# MCU.net
KiCad netlist of a schematic drawn in Altium Designer
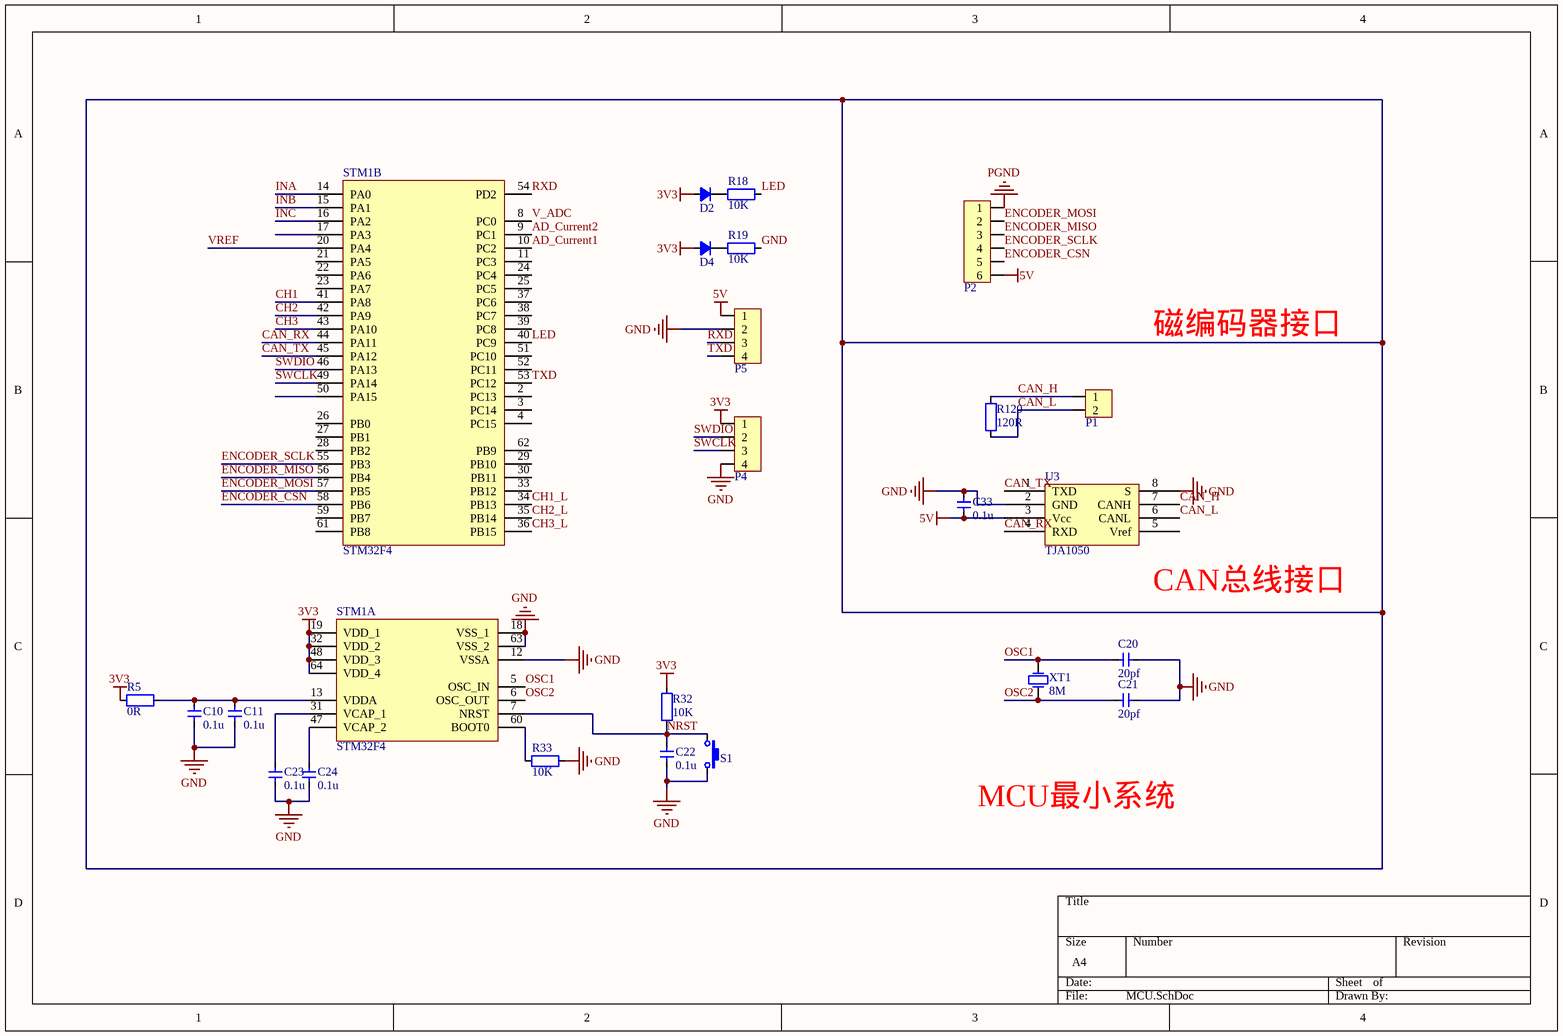
[diagram p0: MCU.SchDoc]

(export (version "E")
  (design (tool "Eeschema 10.0.6"))
  (components
    (comp (ref "C10")
      (value "0.1u")
      (footprint "PCB_PassiveCap:CAP_0603")
      (description "Capacitor")
      (fields (field (name "Comment") "Cap_0603"))
      (libsource (lib "SCH_Passive") (part "Cap_0603"))
    )
    (comp (ref "C11")
      (value "0.1u")
      (footprint "PCB_PassiveCap:CAP_0603")
      (description "Capacitor")
      (fields (field (name "Comment") "Cap_0603"))
      (libsource (lib "SCH_Passive") (part "Cap_0603"))
    )
    (comp (ref "C20")
      (value "20pf")
      (footprint "PCB_PassiveCap:CAP_0603")
      (description "Capacitor")
      (fields (field (name "Comment") "Cap_0603"))
      (libsource (lib "SCH_Passive") (part "Cap_0603"))
    )
    (comp (ref "C21")
      (value "20pf")
      (footprint "PCB_PassiveCap:CAP_0603")
      (description "Capacitor")
      (fields (field (name "Comment") "Cap_0603"))
      (libsource (lib "SCH_Passive") (part "Cap_0603"))
    )
    (comp (ref "C22")
      (value "0.1u")
      (footprint "PCB_PassiveCap:CAP_0603")
      (description "Capacitor")
      (fields (field (name "Comment") "Cap_0603"))
      (libsource (lib "SCH_Passive") (part "Cap_0603"))
    )
    (comp (ref "C23")
      (value "0.1u")
      (footprint "PCB_PassiveCap:CAP_0603")
      (description "Capacitor")
      (fields (field (name "Comment") "Cap_0603"))
      (libsource (lib "SCH_Passive") (part "Cap_0603"))
    )
    (comp (ref "C24")
      (value "0.1u")
      (footprint "PCB_PassiveCap:CAP_0603")
      (description "Capacitor")
      (fields (field (name "Comment") "Cap_0603"))
      (libsource (lib "SCH_Passive") (part "Cap_0603"))
    )
    (comp (ref "C33")
      (value "0.1u")
      (footprint "PCB_PassiveCap:CAP_0603")
      (description "Capacitor")
      (fields (field (name "Comment") "Cap_0603"))
      (libsource (lib "SCH_Passive") (part "Cap_0603"))
    )
    (comp (ref "D2")
      (value "D_0805")
      (footprint "LED_0805_YELLOW")
      (libsource (lib "SCH_Active") (part "D_0805"))
    )
    (comp (ref "D4")
      (value "D_0805")
      (footprint "LED_0805_YELLOW")
      (libsource (lib "SCH_Active") (part "D_0805"))
    )
    (comp (ref "P1")
      (value "HDR1x2_2.54")
      (footprint "PCB_ConnectorHDR:HDR1X2_2.54_180")
      (description "Header")
      (libsource (lib "SCH_ConnectorHDR") (part "HDR1x2_2.54"))
    )
    (comp (ref "P2")
      (value "HDR1x6_2.54")
      (footprint "PCB_ConnectorHDR:1.25mm_1X6_SMT")
      (description "Header")
      (libsource (lib "SCH_ConnectorHDR") (part "HDR1x6_2.54T"))
    )
    (comp (ref "P4")
      (value "HDR1x4_2.54")
      (footprint "PCB_ConnectorHDR:HDR1X4_2.54_90")
      (description "Header")
      (libsource (lib "SCH_ConnectorHDR") (part "HDR1x4_2.54"))
    )
    (comp (ref "P5")
      (value "HDR1x4_2.54")
      (footprint "PCB_ConnectorHDR:1.25X4_SMT")
      (description "Header")
      (libsource (lib "SCH_ConnectorHDR") (part "HDR1x4_2.54"))
    )
    (comp (ref "R5")
      (value "0R")
      (footprint "PCB_PassiveRes:RES_0603")
      (description "Resistor")
      (fields (field (name "Comment") "Res_0603"))
      (libsource (lib "") (part "Res_0603_1"))
    )
    (comp (ref "R18")
      (value "10K")
      (footprint "PCB_PassiveRes:RES_0603")
      (description "Resistor")
      (fields (field (name "Comment") "Res_0603"))
      (libsource (lib "") (part "Res_0603_1"))
    )
    (comp (ref "R19")
      (value "10K")
      (footprint "PCB_PassiveRes:RES_0603")
      (description "Resistor")
      (fields (field (name "Comment") "Res_0603"))
      (libsource (lib "") (part "Res_0603_1"))
    )
    (comp (ref "R32")
      (value "10K")
      (footprint "PCB_PassiveRes:RES_0603")
      (description "Resistor")
      (fields (field (name "Comment") "Res_0603"))
      (libsource (lib "SCH_Passive") (part "Res_0603"))
    )
    (comp (ref "R33")
      (value "10K")
      (footprint "PCB_PassiveRes:RES_0603")
      (description "Resistor")
      (fields (field (name "Comment") "Res_0603"))
      (libsource (lib "") (part "Res_0603_1"))
    )
    (comp (ref "R120")
      (value "120R")
      (footprint "PCB_PassiveRes:RES_0603")
      (description "Resistor")
      (fields (field (name "Comment") "Res_0603"))
      (libsource (lib "SCH_Passive") (part "Res_0603"))
    )
    (comp (ref "S1")
      (value "ButtonTACT_3x4x2_180")
      (footprint "PCB_Switch:ButtonTACT_3x4x2_180H")
      (description "Button")
      (libsource (lib "SCH_Switch") (part "ButtonTACT_3x4x2_180"))
    )
    (comp (ref "STM1")
      (value "STM32F4")
      (footprint "PCB_IntegratedCircuit:LQFP_P0.5_64")
      (description "MCU")
      (libsource (lib "SCH_IntegratedCircuit") (part "STM32F405R"))
    )
    (comp (ref "U3")
      (value "TJA1050")
      (footprint "SOP_E150_8")
      (libsource (lib "SCH_IntegratedCircuit") (part "TJA1050"))
    )
    (comp (ref "XT1")
      (value "8M")
      (footprint "PCB_Oscillator:XT_5032_2")
      (description "Crystal Oscillator")
      (fields (field (name "Comment") "XTAL_5032_2P"))
      (libsource (lib "SCH_Oscillator") (part "XTAL_5032_2P"))
    )
  )
  (nets
    (net (code "1") (name "/AD_Current1") (class "Default")
      (node (ref "STM1") (pin "10") (pinfunction "PC2_10") (pintype "passive"))
    )
    (net (code "2") (name "/AD_Current2") (class "Default")
      (node (ref "STM1") (pin "9") (pinfunction "PC1_9") (pintype "passive"))
    )
    (net (code "3") (name "/CAN_H") (class "Default")
      (node (ref "P1") (pin "1") (pinfunction "1_1") (pintype "passive"))
      (node (ref "R120") (pin "1") (pinfunction "1_1") (pintype "passive"))
      (node (ref "U3") (pin "7") (pinfunction "CANH_7") (pintype "passive"))
    )
    (net (code "4") (name "/CAN_L") (class "Default")
      (node (ref "P1") (pin "2") (pinfunction "2_2") (pintype "passive"))
      (node (ref "R120") (pin "2") (pinfunction "2_2") (pintype "passive"))
      (node (ref "U3") (pin "6") (pinfunction "CANL_6") (pintype "passive"))
    )
    (net (code "5") (name "/CAN_RX") (class "Default")
      (node (ref "STM1") (pin "44") (pinfunction "PA11_44") (pintype "passive"))
      (node (ref "U3") (pin "4") (pinfunction "RXD_4") (pintype "passive"))
    )
    (net (code "6") (name "/CAN_TX") (class "Default")
      (node (ref "STM1") (pin "45") (pinfunction "PA12_45") (pintype "passive"))
      (node (ref "U3") (pin "1") (pinfunction "TXD_1") (pintype "passive"))
    )
    (net (code "7") (name "/CH1") (class "Default")
      (node (ref "STM1") (pin "41") (pinfunction "PA8_41") (pintype "passive"))
    )
    (net (code "8") (name "/CH1_L") (class "Default")
      (node (ref "STM1") (pin "34") (pinfunction "PB13_34") (pintype "passive"))
    )
    (net (code "9") (name "/CH2") (class "Default")
      (node (ref "STM1") (pin "42") (pinfunction "PA9_42") (pintype "passive"))
    )
    (net (code "10") (name "/CH2_L") (class "Default")
      (node (ref "STM1") (pin "35") (pinfunction "PB14_35") (pintype "passive"))
    )
    (net (code "11") (name "/CH3") (class "Default")
      (node (ref "STM1") (pin "43") (pinfunction "PA10_43") (pintype "passive"))
    )
    (net (code "12") (name "/CH3_L") (class "Default")
      (node (ref "STM1") (pin "36") (pinfunction "PB15_36") (pintype "passive"))
    )
    (net (code "13") (name "/ENCODER_CSN") (class "Default")
      (node (ref "P2") (pin "5") (pinfunction "5_5") (pintype "passive"))
      (node (ref "STM1") (pin "58") (pinfunction "PB6_58") (pintype "passive"))
    )
    (net (code "14") (name "/ENCODER_MISO") (class "Default")
      (node (ref "P2") (pin "3") (pinfunction "3_3") (pintype "passive"))
      (node (ref "STM1") (pin "56") (pinfunction "PB4_56") (pintype "passive"))
    )
    (net (code "15") (name "/ENCODER_MOSI") (class "Default")
      (node (ref "P2") (pin "2") (pinfunction "2_2") (pintype "passive"))
      (node (ref "STM1") (pin "57") (pinfunction "PB5_57") (pintype "passive"))
    )
    (net (code "16") (name "/ENCODER_SCLK") (class "Default")
      (node (ref "P2") (pin "4") (pinfunction "4_4") (pintype "passive"))
      (node (ref "STM1") (pin "55") (pinfunction "PB3_55") (pintype "passive"))
    )
    (net (code "17") (name "/INA") (class "Default")
      (node (ref "STM1") (pin "14") (pinfunction "PA0_14") (pintype "passive"))
    )
    (net (code "18") (name "/INB") (class "Default")
      (node (ref "STM1") (pin "15") (pinfunction "PA1_15") (pintype "passive"))
    )
    (net (code "19") (name "/INC") (class "Default")
      (node (ref "STM1") (pin "16") (pinfunction "PA2_16") (pintype "passive"))
    )
    (net (code "20") (name "/LED") (class "Default")
      (node (ref "R18") (pin "2") (pinfunction "2_2") (pintype "passive"))
      (node (ref "STM1") (pin "40") (pinfunction "PC9_40") (pintype "passive"))
    )
    (net (code "21") (name "/NRST") (class "Default")
      (node (ref "C22") (pin "2") (pinfunction "2_2") (pintype "passive"))
      (node (ref "R32") (pin "2") (pinfunction "2_2") (pintype "passive"))
      (node (ref "S1") (pin "1") (pinfunction "1_1") (pintype "passive"))
      (node (ref "STM1") (pin "7") (pinfunction "NRST_7") (pintype "passive"))
    )
    (net (code "22") (name "/OSC1") (class "Default")
      (node (ref "C20") (pin "2") (pinfunction "2_2") (pintype "passive"))
      (node (ref "STM1") (pin "5") (pinfunction "OSC_IN_5") (pintype "passive"))
      (node (ref "XT1") (pin "2") (pinfunction "OSC2_2") (pintype "passive"))
    )
    (net (code "23") (name "/OSC2") (class "Default")
      (node (ref "C21") (pin "2") (pinfunction "2_2") (pintype "passive"))
      (node (ref "STM1") (pin "6") (pinfunction "OSC_OUT_6") (pintype "passive"))
      (node (ref "XT1") (pin "1") (pinfunction "OSC1_1") (pintype "passive"))
    )
    (net (code "24") (name "/RXD") (class "Default")
      (node (ref "P5") (pin "3") (pinfunction "3_3") (pintype "passive"))
      (node (ref "STM1") (pin "54") (pinfunction "PD2_54") (pintype "passive"))
    )
    (net (code "25") (name "/SWCLK") (class "Default")
      (node (ref "P4") (pin "3") (pinfunction "3_3") (pintype "passive"))
      (node (ref "STM1") (pin "49") (pinfunction "PA14_49") (pintype "passive"))
    )
    (net (code "26") (name "/SWDIO") (class "Default")
      (node (ref "P4") (pin "2") (pinfunction "2_2") (pintype "passive"))
      (node (ref "STM1") (pin "46") (pinfunction "PA13_46") (pintype "passive"))
    )
    (net (code "27") (name "/TXD") (class "Default")
      (node (ref "P5") (pin "4") (pinfunction "4_4") (pintype "passive"))
      (node (ref "STM1") (pin "53") (pinfunction "PC12_53") (pintype "passive"))
    )
    (net (code "28") (name "/VREF") (class "Default")
      (node (ref "STM1") (pin "20") (pinfunction "PA4_20") (pintype "passive"))
    )
    (net (code "29") (name "/V_ADC") (class "Default")
      (node (ref "STM1") (pin "8") (pinfunction "PC0_8") (pintype "passive"))
    )
    (net (code "30") (name "3V3") (class "Default")
      (node (ref "D2") (pin "1") (pinfunction "A_1") (pintype "passive"))
      (node (ref "D4") (pin "1") (pinfunction "A_1") (pintype "passive"))
      (node (ref "P4") (pin "1") (pinfunction "1_1") (pintype "passive"))
      (node (ref "R32") (pin "1") (pinfunction "1_1") (pintype "passive"))
      (node (ref "R5") (pin "1") (pinfunction "1_1") (pintype "passive"))
      (node (ref "STM1") (pin "19") (pinfunction "VDD_1_19") (pintype "passive"))
      (node (ref "STM1") (pin "32") (pinfunction "VDD_2_32") (pintype "passive"))
      (node (ref "STM1") (pin "48") (pinfunction "VDD_3_48") (pintype "passive"))
      (node (ref "STM1") (pin "64") (pinfunction "VDD_4_64") (pintype "passive"))
    )
    (net (code "31") (name "5V") (class "Default")
      (node (ref "C33") (pin "1") (pinfunction "1_1") (pintype "passive"))
      (node (ref "P2") (pin "6") (pinfunction "6_6") (pintype "passive"))
      (node (ref "P5") (pin "1") (pinfunction "1_1") (pintype "passive"))
      (node (ref "U3") (pin "3") (pinfunction "Vcc_3") (pintype "passive"))
    )
    (net (code "32") (name "GND") (class "Default")
      (node (ref "C10") (pin "1") (pinfunction "1_1") (pintype "passive"))
      (node (ref "C11") (pin "1") (pinfunction "1_1") (pintype "passive"))
      (node (ref "C20") (pin "1") (pinfunction "1_1") (pintype "passive"))
      (node (ref "C21") (pin "1") (pinfunction "1_1") (pintype "passive"))
      (node (ref "C22") (pin "1") (pinfunction "1_1") (pintype "passive"))
      (node (ref "C23") (pin "2") (pinfunction "2_2") (pintype "passive"))
      (node (ref "C24") (pin "2") (pinfunction "2_2") (pintype "passive"))
      (node (ref "C33") (pin "2") (pinfunction "2_2") (pintype "passive"))
      (node (ref "P4") (pin "4") (pinfunction "4_4") (pintype "passive"))
      (node (ref "P5") (pin "2") (pinfunction "2_2") (pintype "passive"))
      (node (ref "R19") (pin "2") (pinfunction "2_2") (pintype "passive"))
      (node (ref "R33") (pin "2") (pinfunction "2_2") (pintype "passive"))
      (node (ref "S1") (pin "2") (pinfunction "2_2") (pintype "passive"))
      (node (ref "STM1") (pin "12") (pinfunction "VSSA_12") (pintype "passive"))
      (node (ref "STM1") (pin "18") (pinfunction "VSS_1_18") (pintype "passive"))
      (node (ref "STM1") (pin "63") (pinfunction "VSS_2_63") (pintype "passive"))
      (node (ref "U3") (pin "2") (pinfunction "GND_2") (pintype "passive"))
      (node (ref "U3") (pin "8") (pinfunction "S_8") (pintype "passive"))
    )
    (net (code "33") (name "Net-(D2-K)") (class "Default")
      (node (ref "D2") (pin "2") (pinfunction "K_2") (pintype "passive"))
      (node (ref "R18") (pin "1") (pinfunction "1_1") (pintype "passive"))
    )
    (net (code "34") (name "Net-(D4-K)") (class "Default")
      (node (ref "D4") (pin "2") (pinfunction "K_2") (pintype "passive"))
      (node (ref "R19") (pin "1") (pinfunction "1_1") (pintype "passive"))
    )
    (net (code "35") (name "Net-(STM1A-BOOT0)") (class "Default")
      (node (ref "R33") (pin "1") (pinfunction "1_1") (pintype "passive"))
      (node (ref "STM1") (pin "60") (pinfunction "BOOT0_60") (pintype "passive"))
    )
    (net (code "36") (name "Net-(STM1A-VCAP_1)") (class "Default")
      (node (ref "C23") (pin "1") (pinfunction "1_1") (pintype "passive"))
      (node (ref "STM1") (pin "31") (pinfunction "VCAP_1_31") (pintype "passive"))
    )
    (net (code "37") (name "Net-(STM1A-VCAP_2)") (class "Default")
      (node (ref "C24") (pin "1") (pinfunction "1_1") (pintype "passive"))
      (node (ref "STM1") (pin "47") (pinfunction "VCAP_2_47") (pintype "passive"))
    )
    (net (code "38") (name "Net-(STM1A-VDDA)") (class "Default")
      (node (ref "C10") (pin "2") (pinfunction "2_2") (pintype "passive"))
      (node (ref "C11") (pin "2") (pinfunction "2_2") (pintype "passive"))
      (node (ref "R5") (pin "2") (pinfunction "2_2") (pintype "passive"))
      (node (ref "STM1") (pin "13") (pinfunction "VDDA_13") (pintype "passive"))
    )
    (net (code "39") (name "PGND") (class "Default")
      (node (ref "P2") (pin "1") (pinfunction "1_1") (pintype "passive"))
    )
    (net (code "40") (name "unconnected-(STM1B-PA3-Pad17)") (class "Default")
      (node (ref "STM1") (pin "17") (pinfunction "PA3_17") (pintype "passive"))
    )
    (net (code "41") (name "unconnected-(STM1B-PA5-Pad21)") (class "Default")
      (node (ref "STM1") (pin "21") (pinfunction "PA5_21") (pintype "passive"))
    )
    (net (code "42") (name "unconnected-(STM1B-PA6-Pad22)") (class "Default")
      (node (ref "STM1") (pin "22") (pinfunction "PA6_22") (pintype "passive"))
    )
    (net (code "43") (name "unconnected-(STM1B-PA7-Pad23)") (class "Default")
      (node (ref "STM1") (pin "23") (pinfunction "PA7_23") (pintype "passive"))
    )
    (net (code "44") (name "unconnected-(STM1B-PA15-Pad50)") (class "Default")
      (node (ref "STM1") (pin "50") (pinfunction "PA15_50") (pintype "passive"))
    )
    (net (code "45") (name "unconnected-(STM1B-PB0-Pad26)") (class "Default")
      (node (ref "STM1") (pin "26") (pinfunction "PB0_26") (pintype "passive"))
    )
    (net (code "46") (name "unconnected-(STM1B-PB1-Pad27)") (class "Default")
      (node (ref "STM1") (pin "27") (pinfunction "PB1_27") (pintype "passive"))
    )
    (net (code "47") (name "unconnected-(STM1B-PB2-Pad28)") (class "Default")
      (node (ref "STM1") (pin "28") (pinfunction "PB2_28") (pintype "passive"))
    )
    (net (code "48") (name "unconnected-(STM1B-PB7-Pad59)") (class "Default")
      (node (ref "STM1") (pin "59") (pinfunction "PB7_59") (pintype "passive"))
    )
    (net (code "49") (name "unconnected-(STM1B-PB8-Pad61)") (class "Default")
      (node (ref "STM1") (pin "61") (pinfunction "PB8_61") (pintype "passive"))
    )
    (net (code "50") (name "unconnected-(STM1B-PB9-Pad62)") (class "Default")
      (node (ref "STM1") (pin "62") (pinfunction "PB9_62") (pintype "passive"))
    )
    (net (code "51") (name "unconnected-(STM1B-PB10-Pad29)") (class "Default")
      (node (ref "STM1") (pin "29") (pinfunction "PB10_29") (pintype "passive"))
    )
    (net (code "52") (name "unconnected-(STM1B-PB11-Pad30)") (class "Default")
      (node (ref "STM1") (pin "30") (pinfunction "PB11_30") (pintype "passive"))
    )
    (net (code "53") (name "unconnected-(STM1B-PB12-Pad33)") (class "Default")
      (node (ref "STM1") (pin "33") (pinfunction "PB12_33") (pintype "passive"))
    )
    (net (code "54") (name "unconnected-(STM1B-PC3-Pad11)") (class "Default")
      (node (ref "STM1") (pin "11") (pinfunction "PC3_11") (pintype "passive"))
    )
    (net (code "55") (name "unconnected-(STM1B-PC4-Pad24)") (class "Default")
      (node (ref "STM1") (pin "24") (pinfunction "PC4_24") (pintype "passive"))
    )
    (net (code "56") (name "unconnected-(STM1B-PC5-Pad25)") (class "Default")
      (node (ref "STM1") (pin "25") (pinfunction "PC5_25") (pintype "passive"))
    )
    (net (code "57") (name "unconnected-(STM1B-PC6-Pad37)") (class "Default")
      (node (ref "STM1") (pin "37") (pinfunction "PC6_37") (pintype "passive"))
    )
    (net (code "58") (name "unconnected-(STM1B-PC7-Pad38)") (class "Default")
      (node (ref "STM1") (pin "38") (pinfunction "PC7_38") (pintype "passive"))
    )
    (net (code "59") (name "unconnected-(STM1B-PC8-Pad39)") (class "Default")
      (node (ref "STM1") (pin "39") (pinfunction "PC8_39") (pintype "passive"))
    )
    (net (code "60") (name "unconnected-(STM1B-PC10-Pad51)") (class "Default")
      (node (ref "STM1") (pin "51") (pinfunction "PC10_51") (pintype "passive"))
    )
    (net (code "61") (name "unconnected-(STM1B-PC11-Pad52)") (class "Default")
      (node (ref "STM1") (pin "52") (pinfunction "PC11_52") (pintype "passive"))
    )
    (net (code "62") (name "unconnected-(STM1B-PC13-Pad2)") (class "Default")
      (node (ref "STM1") (pin "2") (pinfunction "PC13_2") (pintype "passive"))
    )
    (net (code "63") (name "unconnected-(STM1B-PC14-Pad3)") (class "Default")
      (node (ref "STM1") (pin "3") (pinfunction "PC14_3") (pintype "passive"))
    )
    (net (code "64") (name "unconnected-(STM1B-PC15-Pad4)") (class "Default")
      (node (ref "STM1") (pin "4") (pinfunction "PC15_4") (pintype "passive"))
    )
    (net (code "65") (name "unconnected-(U3-Vref-Pad5)") (class "Default")
      (node (ref "U3") (pin "5") (pinfunction "Vref_5") (pintype "passive"))
    )
  )
)
